# waterius-factory-2_0.net
KiCad netlist of a schematic drawn in EAGLE
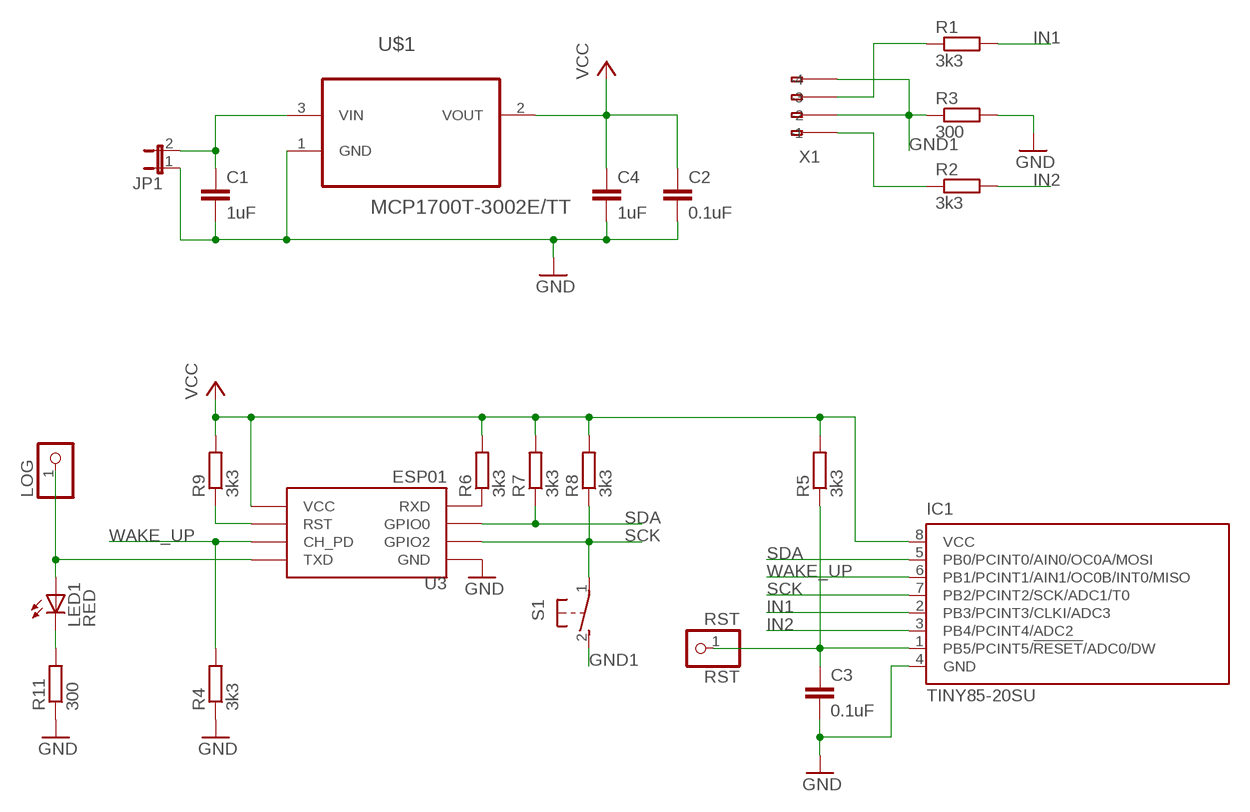
[diagram p0: schematic, sheet 1]

(export (version "E")
  (design (tool "Eeschema 10.0.6"))
  (components
    (comp (ref "C1")
      (value "1uF")
      (footprint "eagle-import:C0805")
      (libsource (lib "eagle-import") (part "C-EUC0805"))
    )
    (comp (ref "C2")
      (value "0.1uF")
      (footprint "eagle-import:C0805")
      (libsource (lib "eagle-import") (part "C-EUC0805"))
    )
    (comp (ref "C3")
      (value "0.1uF")
      (footprint "eagle-import:C0805")
      (libsource (lib "eagle-import") (part "C-EUC0805"))
    )
    (comp (ref "C4")
      (value "1uF")
      (footprint "eagle-import:C0805")
      (libsource (lib "eagle-import") (part "C-EUC0805"))
    )
    (comp (ref "IC1")
      (value "TINY85-20SU")
      (footprint "eagle-import:8S2")
      (fields (field (name "MPN") "ATTINY13-20SU"))
      (libsource (lib "eagle-import") (part "TINY13SU-20"))
    )
    (comp (ref "JP1")
      (value "JP1E")
      (footprint "eagle-import:JP1")
      (libsource (lib "eagle-import") (part "JP1E"))
    )
    (comp (ref "LED1")
      (value "RED")
      (footprint "eagle-import:LED3MM")
      (libsource (lib "eagle-import") (part "LED3MM"))
    )
    (comp (ref "LOG")
      (value "PINHD-1X1")
      (footprint "eagle-import:1X01")
      (libsource (lib "eagle-import") (part "PINHD-1X1"))
    )
    (comp (ref "R1")
      (value "3k3")
      (footprint "eagle-import:R0805")
      (libsource (lib "eagle-import") (part "R-EU_R0805"))
    )
    (comp (ref "R2")
      (value "3k3")
      (footprint "eagle-import:R0805")
      (libsource (lib "eagle-import") (part "R-EU_R0805"))
    )
    (comp (ref "R3")
      (value "300")
      (footprint "eagle-import:R0805")
      (libsource (lib "eagle-import") (part "R-EU_R0805"))
    )
    (comp (ref "R4")
      (value "3k3")
      (footprint "eagle-import:R0805")
      (libsource (lib "eagle-import") (part "R-EU_R0805"))
    )
    (comp (ref "R5")
      (value "3k3")
      (footprint "eagle-import:R0805")
      (libsource (lib "eagle-import") (part "R-EU_R0805"))
    )
    (comp (ref "R6")
      (value "3k3")
      (footprint "eagle-import:R0805")
      (libsource (lib "eagle-import") (part "R-EU_R0805"))
    )
    (comp (ref "R7")
      (value "3k3")
      (footprint "eagle-import:R0805")
      (libsource (lib "eagle-import") (part "R-EU_R0805"))
    )
    (comp (ref "R8")
      (value "3k3")
      (footprint "eagle-import:R0805")
      (libsource (lib "eagle-import") (part "R-EU_R0805"))
    )
    (comp (ref "R9")
      (value "3k3")
      (footprint "eagle-import:R0805")
      (libsource (lib "eagle-import") (part "R-EU_R0805"))
    )
    (comp (ref "R11")
      (value "300")
      (footprint "eagle-import:R0805")
      (libsource (lib "eagle-import") (part "R-EU_R0805"))
    )
    (comp (ref "RST")
      (value "RST")
      (footprint "eagle-import:1X01")
      (libsource (lib "eagle-import") (part "PINHD-1X1"))
    )
    (comp (ref "S1")
      (value "31-XX")
      (footprint "eagle-import:B3F-31XX")
      (fields (field (name "MPN") "B3F-3100"))
      (libsource (lib "eagle-import") (part "31-XX"))
    )
    (comp (ref "U$1")
      (value "MCP1700T-3002E/TT")
      (footprint "eagle-import:SOT95P237X112-3N")
      (fields (field (name "MF") "Microchip"))
      (libsource (lib "eagle-import") (part "MCP1700T-3002E/TT"))
    )
    (comp (ref "U3")
      (value "ESP01")
      (footprint "eagle-import:ESP01")
      (libsource (lib "eagle-import") (part "ESP01"))
    )
    (comp (ref "X1")
      (value "233-104")
      (footprint "eagle-import:233-104")
      (libsource (lib "eagle-import") (part "233-104"))
    )
  )
  (nets
    (net (code "1") (name "/GND1") (class "Default")
      (node (ref "R3") (pin "1") (pinfunction "1_1") (pintype "passive"))
      (node (ref "S1") (pin "2") (pinfunction "S_2") (pintype "passive"))
      (node (ref "X1") (pin "A2") (pinfunction "-2_A2") (pintype "passive"))
      (node (ref "X1") (pin "A4") (pinfunction "-4_A4") (pintype "passive"))
    )
    (net (code "2") (name "/IN1") (class "Default")
      (node (ref "IC1") (pin "2") (pinfunction "PB3/PCINT3/CLKI/ADC3_2") (pintype "bidirectional"))
      (node (ref "R1") (pin "2") (pinfunction "2_2") (pintype "passive"))
    )
    (net (code "3") (name "/IN2") (class "Default")
      (node (ref "IC1") (pin "3") (pinfunction "PB4/PCINT4/ADC2_3") (pintype "bidirectional"))
      (node (ref "R2") (pin "2") (pinfunction "2_2") (pintype "passive"))
    )
    (net (code "4") (name "/SCK") (class "Default")
      (node (ref "IC1") (pin "7") (pinfunction "PB2/PCINT2/SCK/ADC1/T0_7") (pintype "bidirectional"))
      (node (ref "R8") (pin "1") (pinfunction "1_1") (pintype "passive"))
      (node (ref "S1") (pin "1") (pinfunction "P_1") (pintype "passive"))
      (node (ref "U3") (pin "GPIO2") (pinfunction "GPIO2_GPIO2") (pintype "bidirectional"))
    )
    (net (code "5") (name "/SDA") (class "Default")
      (node (ref "IC1") (pin "5") (pinfunction "PB0/PCINT0/AIN0/OC0A/MOSI_5") (pintype "bidirectional"))
      (node (ref "R7") (pin "1") (pinfunction "1_1") (pintype "passive"))
      (node (ref "U3") (pin "GPIO0") (pinfunction "GPIO0_GPIO0") (pintype "bidirectional"))
    )
    (net (code "6") (name "/WAKE_UP") (class "Default")
      (node (ref "IC1") (pin "6") (pinfunction "PB1/PCINT1/AIN1/OC0B/INT0/MISO_6") (pintype "bidirectional"))
      (node (ref "R4") (pin "2") (pinfunction "2_2") (pintype "passive"))
      (node (ref "U3") (pin "CH_PD") (pinfunction "CH_PD_CH_PD") (pintype "bidirectional"))
    )
    (net (code "7") (name "GND") (class "Default")
      (node (ref "C1") (pin "2") (pinfunction "2_2") (pintype "passive"))
      (node (ref "C2") (pin "2") (pinfunction "2_2") (pintype "passive"))
      (node (ref "C3") (pin "2") (pinfunction "2_2") (pintype "passive"))
      (node (ref "C4") (pin "2") (pinfunction "2_2") (pintype "passive"))
      (node (ref "IC1") (pin "4") (pinfunction "GND_4") (pintype "power_in"))
      (node (ref "JP1") (pin "1") (pinfunction "1_1") (pintype "passive"))
      (node (ref "R11") (pin "1") (pinfunction "1_1") (pintype "passive"))
      (node (ref "R3") (pin "2") (pinfunction "2_2") (pintype "passive"))
      (node (ref "R4") (pin "1") (pinfunction "1_1") (pintype "passive"))
      (node (ref "U$1") (pin "1") (pinfunction "GND_1") (pintype "passive"))
      (node (ref "U3") (pin "GND") (pinfunction "GND_GND") (pintype "bidirectional"))
    )
    (net (code "8") (name "Net-(IC1-PB5{slash}PCINT5{slash}~{RESET}{slash}ADC0{slash}DW)") (class "Default")
      (node (ref "C3") (pin "1") (pinfunction "1_1") (pintype "passive"))
      (node (ref "IC1") (pin "1") (pinfunction "PB5/PCINT5/~{RESET}/ADC0/DW_1") (pintype "bidirectional"))
      (node (ref "R5") (pin "1") (pinfunction "1_1") (pintype "passive"))
      (node (ref "RST") (pin "1") (pinfunction "1_1") (pintype "passive"))
    )
    (net (code "9") (name "Net-(LED1-C)") (class "Default")
      (node (ref "LED1") (pin "K") (pinfunction "C_K") (pintype "passive"))
      (node (ref "R11") (pin "2") (pinfunction "2_2") (pintype "passive"))
    )
    (net (code "10") (name "Net-(R9-Pad1)") (class "Default")
      (node (ref "R9") (pin "1") (pinfunction "1_1") (pintype "passive"))
      (node (ref "U3") (pin "RST") (pinfunction "RST_RST") (pintype "bidirectional"))
    )
    (net (code "11") (name "Net-(U$1-VIN)") (class "Default")
      (node (ref "C1") (pin "1") (pinfunction "1_1") (pintype "passive"))
      (node (ref "JP1") (pin "2") (pinfunction "2_2") (pintype "passive"))
      (node (ref "U$1") (pin "3") (pinfunction "VIN_3") (pintype "input"))
    )
    (net (code "12") (name "Net-(U3-RXD)") (class "Default")
      (node (ref "R6") (pin "1") (pinfunction "1_1") (pintype "passive"))
      (node (ref "U3") (pin "RX") (pinfunction "RXD_RX") (pintype "bidirectional"))
    )
    (net (code "13") (name "Net-(U3-TXD)") (class "Default")
      (node (ref "LED1") (pin "A") (pinfunction "A_A") (pintype "passive"))
      (node (ref "LOG") (pin "1") (pinfunction "1_1") (pintype "passive"))
      (node (ref "U3") (pin "TX") (pinfunction "TXD_TX") (pintype "bidirectional"))
    )
    (net (code "14") (name "Net-(X1--1)") (class "Default")
      (node (ref "R2") (pin "1") (pinfunction "1_1") (pintype "passive"))
      (node (ref "X1") (pin "A1") (pinfunction "-1_A1") (pintype "passive"))
    )
    (net (code "15") (name "Net-(X1--3)") (class "Default")
      (node (ref "R1") (pin "1") (pinfunction "1_1") (pintype "passive"))
      (node (ref "X1") (pin "A3") (pinfunction "-3_A3") (pintype "passive"))
    )
    (net (code "16") (name "VCC") (class "Default")
      (node (ref "C2") (pin "1") (pinfunction "1_1") (pintype "passive"))
      (node (ref "C4") (pin "1") (pinfunction "1_1") (pintype "passive"))
      (node (ref "IC1") (pin "8") (pinfunction "VCC_8") (pintype "power_in"))
      (node (ref "R5") (pin "2") (pinfunction "2_2") (pintype "passive"))
      (node (ref "R6") (pin "2") (pinfunction "2_2") (pintype "passive"))
      (node (ref "R7") (pin "2") (pinfunction "2_2") (pintype "passive"))
      (node (ref "R8") (pin "2") (pinfunction "2_2") (pintype "passive"))
      (node (ref "R9") (pin "2") (pinfunction "2_2") (pintype "passive"))
      (node (ref "U$1") (pin "2") (pinfunction "VOUT_2") (pintype "output"))
      (node (ref "U3") (pin "VCC") (pinfunction "VCC_VCC") (pintype "bidirectional"))
    )
    (net (code "17") (name "unconnected-(X1-B-1-PadB1)") (class "Default")
      (node (ref "X1") (pin "B1") (pinfunction "B-1_B1") (pintype "passive"))
    )
    (net (code "18") (name "unconnected-(X1-B-2-PadB2)") (class "Default")
      (node (ref "X1") (pin "B2") (pinfunction "B-2_B2") (pintype "passive"))
    )
    (net (code "19") (name "unconnected-(X1-B-3-PadB3)") (class "Default")
      (node (ref "X1") (pin "B3") (pinfunction "B-3_B3") (pintype "passive"))
    )
    (net (code "20") (name "unconnected-(X1-B-4-PadB4)") (class "Default")
      (node (ref "X1") (pin "B4") (pinfunction "B-4_B4") (pintype "passive"))
    )
  )
)
